# SPX3819M5-L-3-3.net
KiCad netlist of a schematic drawn in EasyEDA Pro
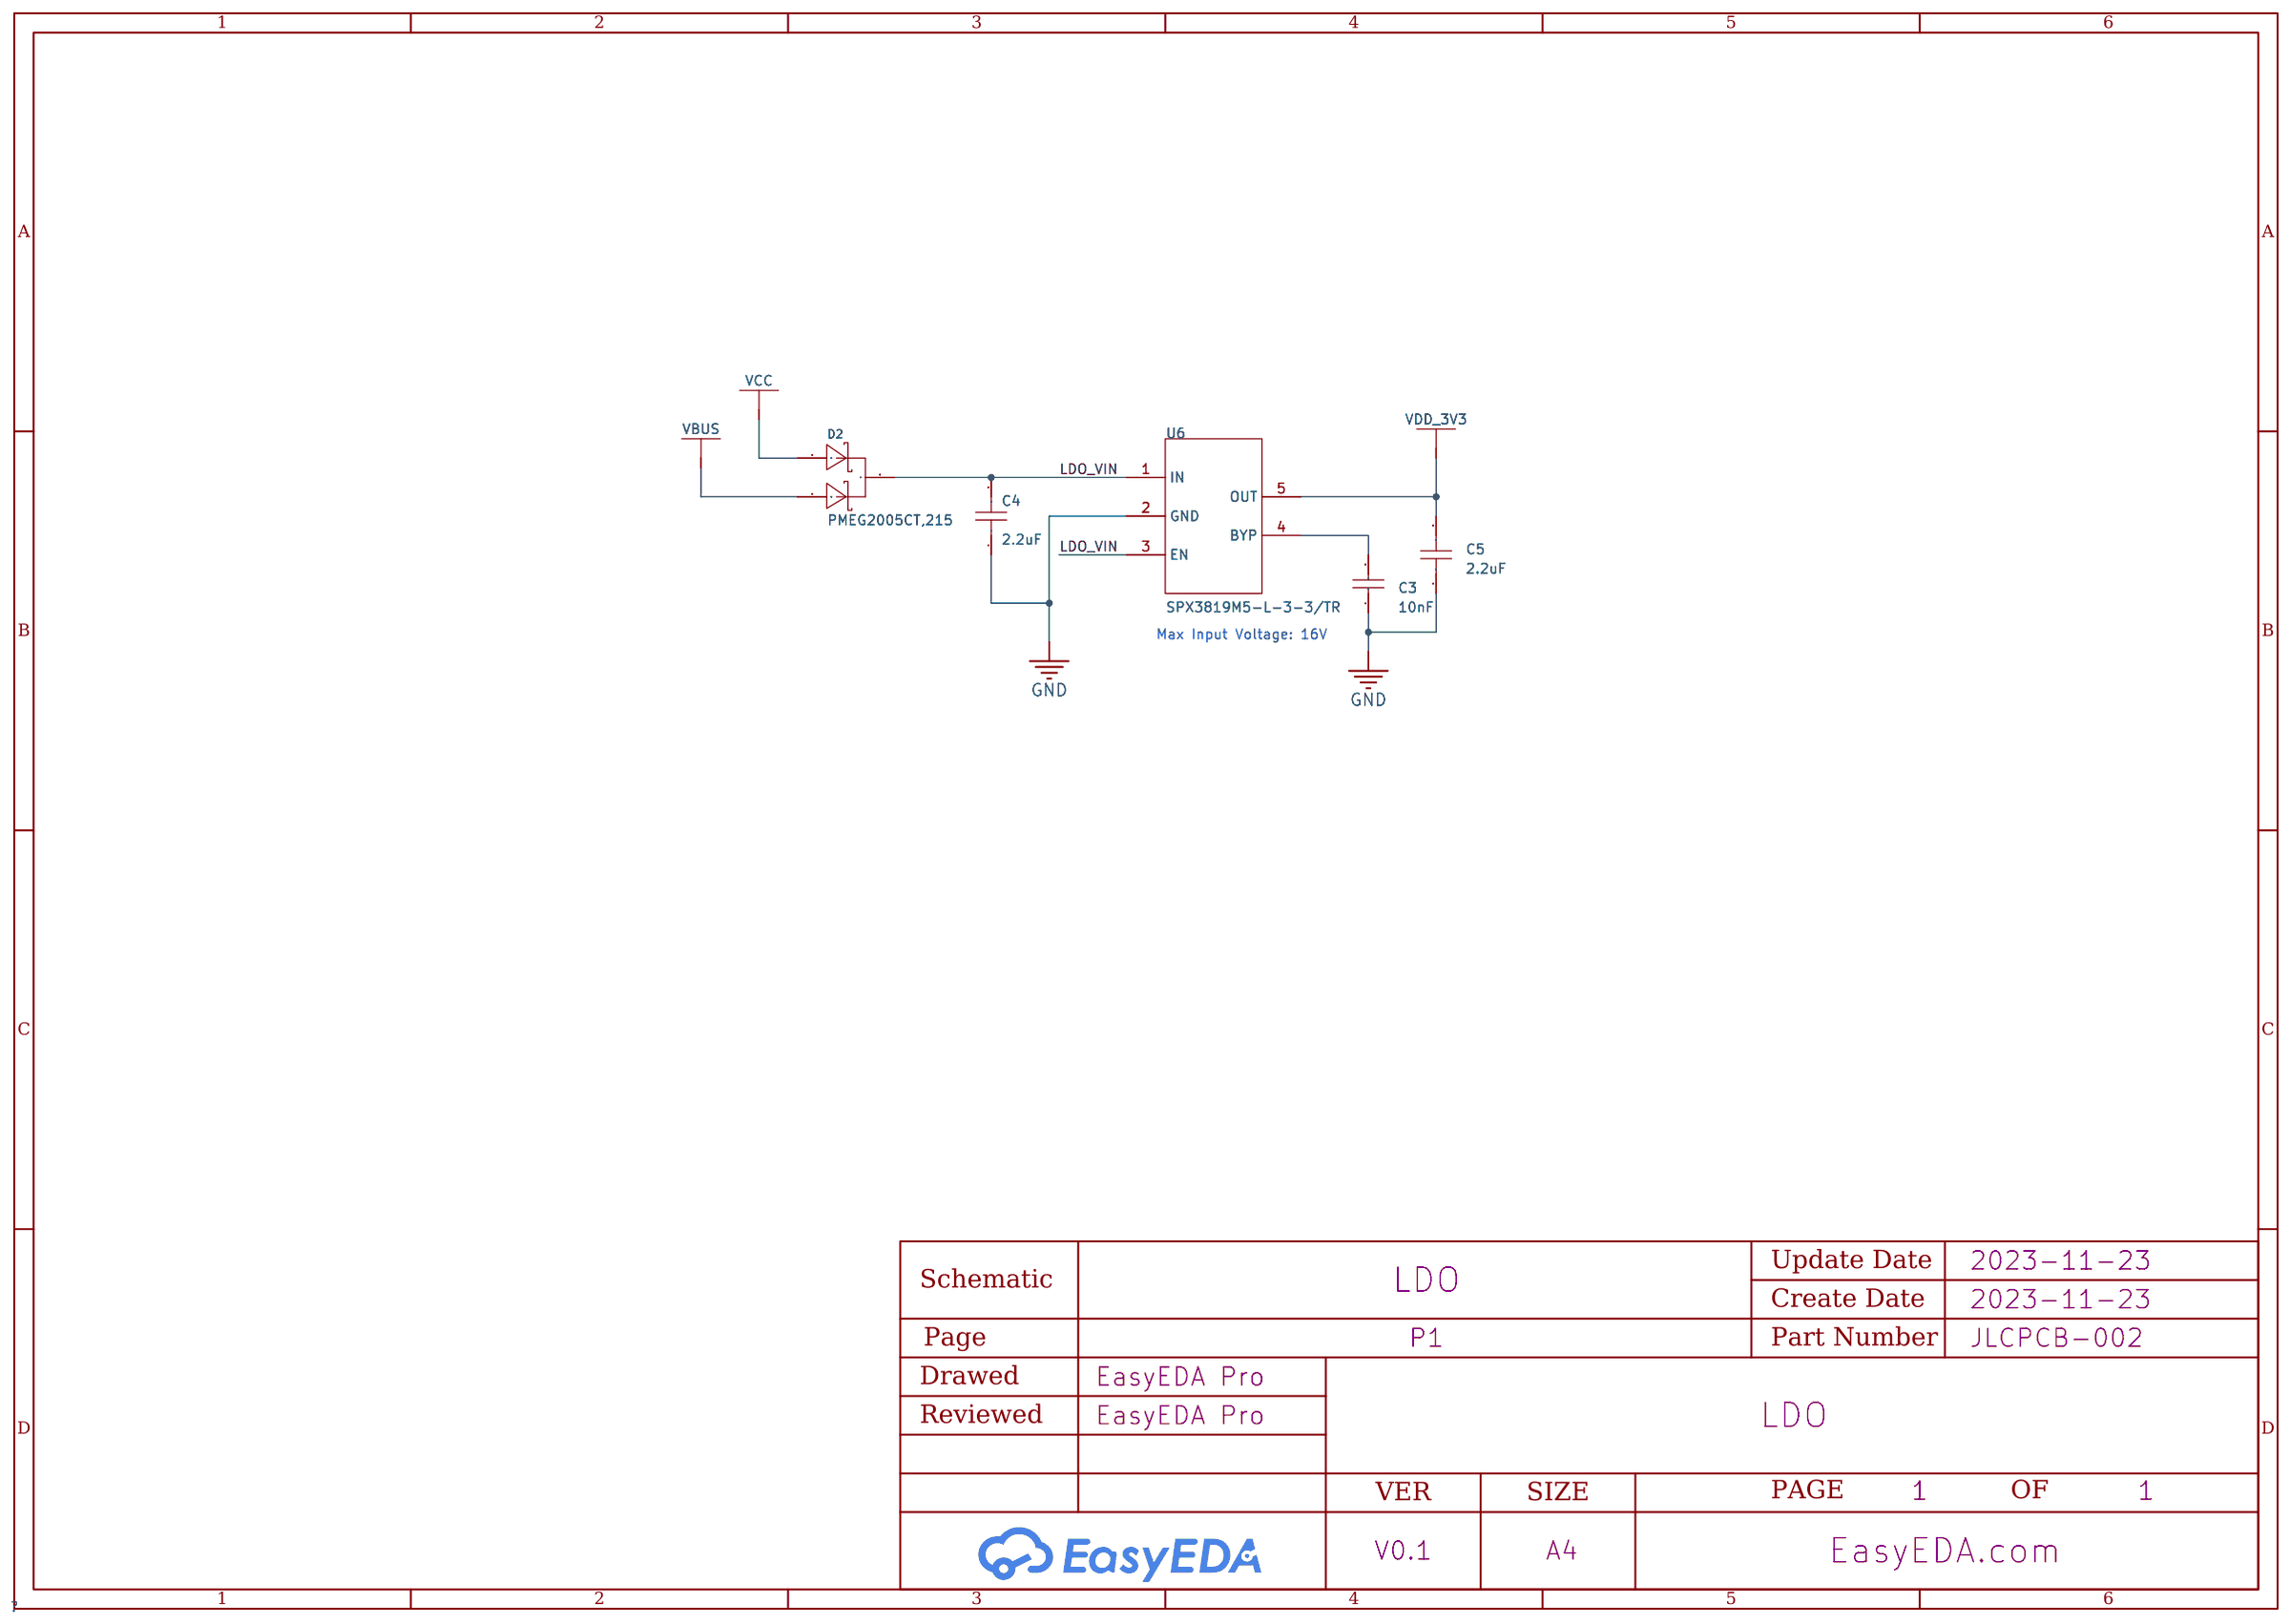
[diagram p0: schematic sheet]

(export (version "E")
  (design (tool "Eeschema 10.0.6"))
  (components
    (comp (ref "C3")
      (value "10nF")
      (footprint "easyedapro:C0402")
      (fields
        (field (name "Manufacturer Part") "CL05B103KB5NNNC")
        (field (name "Manufacturer") "SAMSUNG(三星)")
      )
      (libsource (lib "easyedapro") (part "CL05B103KB5NNNC"))
    )
    (comp (ref "C4")
      (value "2.2uF")
      (footprint "easyedapro:C0603")
      (fields
        (field (name "Manufacturer Part") "CL10A225KA8NNNC")
        (field (name "Manufacturer") "SAMSUNG(三星)")
      )
      (libsource (lib "easyedapro") (part "CL10A225KA8NNNC"))
    )
    (comp (ref "C5")
      (value "2.2uF")
      (footprint "easyedapro:C0603")
      (fields
        (field (name "Manufacturer Part") "CL10A225KA8NNNC")
        (field (name "Manufacturer") "SAMSUNG(三星)")
      )
      (libsource (lib "easyedapro") (part "CL10A225KA8NNNC"))
    )
    (comp (ref "D2")
      (value "PMEG2005CT,215")
      (footprint "easyedapro:TO-236AB_L2.9-W1.3-P0.95-LS2.3-BR")
      (fields (field (name "Manufacturer") "Nexperia(安世)"))
      (libsource (lib "easyedapro") (part "PMEG2005CT,215"))
    )
    (comp (ref "U6")
      (value "SPX3819M5-L-3-3/TR")
      (footprint "easyedapro:SOT-23-5_L3.0-W1.7-P0.95-LS2.8-BL")
      (fields (field (name "Manufacturer") "MaxLinear"))
      (libsource (lib "easyedapro") (part "SPX3819M5-L-3-3/TR"))
    )
  )
  (nets
    (net (code "1") (name "/LDO_VIN") (class "Default")
      (node (ref "C4") (pin "2") (pinfunction "2_2") (pintype "input"))
      (node (ref "D2") (pin "3") (pinfunction "K_3") (pintype "input"))
      (node (ref "U6") (pin "1") (pinfunction "IN_1") (pintype "input"))
      (node (ref "U6") (pin "3") (pinfunction "EN_3") (pintype "input"))
    )
    (net (code "2") (name "GND") (class "Default")
      (node (ref "C3") (pin "1") (pinfunction "1_1") (pintype "input"))
      (node (ref "C4") (pin "1") (pinfunction "1_1") (pintype "input"))
      (node (ref "C5") (pin "1") (pinfunction "1_1") (pintype "input"))
      (node (ref "U6") (pin "2") (pinfunction "GND_2") (pintype "input"))
    )
    (net (code "3") (name "Net-(U6-BYP)") (class "Default")
      (node (ref "C3") (pin "2") (pinfunction "2_2") (pintype "input"))
      (node (ref "U6") (pin "4") (pinfunction "BYP_4") (pintype "input"))
    )
    (net (code "4") (name "VBUS") (class "Default")
      (node (ref "D2") (pin "2") (pinfunction "A2_2") (pintype "input"))
    )
    (net (code "5") (name "VCC") (class "Default")
      (node (ref "D2") (pin "1") (pinfunction "A1_1") (pintype "input"))
    )
    (net (code "6") (name "VDD_3V3") (class "Default")
      (node (ref "C5") (pin "2") (pinfunction "2_2") (pintype "input"))
      (node (ref "U6") (pin "5") (pinfunction "OUT_5") (pintype "input"))
    )
  )
)
